# Grove_-_Mega_shield_v1_1.net
KiCad netlist of a schematic drawn in EAGLE
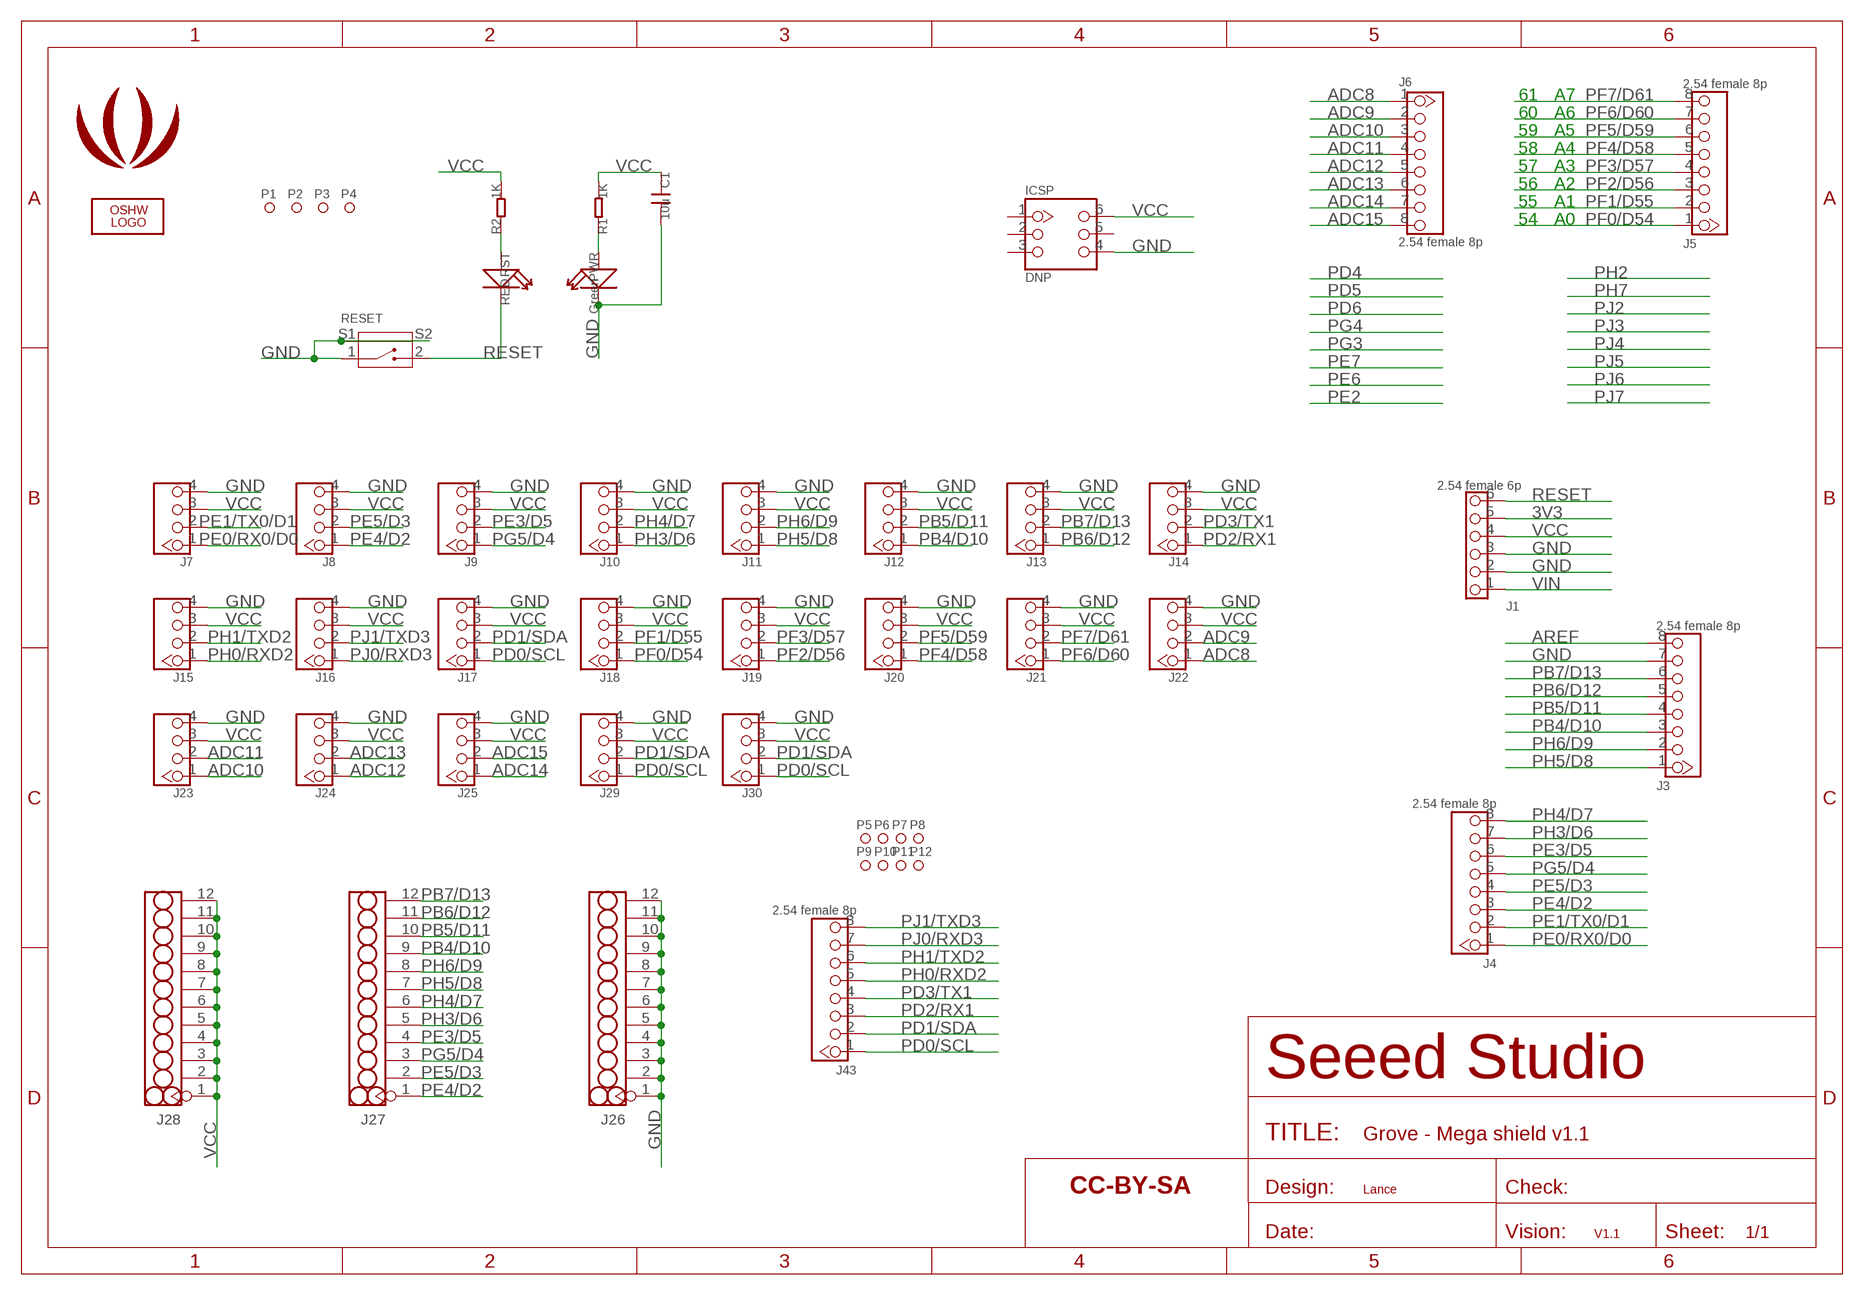
[diagram p0: schematic, sheet 1]

(export (version "E")
  (design (tool "Eeschema 10.0.6"))
  (components
    (comp (ref "C1")
      (value "10u")
      (footprint "eagle-import:0805")
      (libsource (lib "eagle-import") (part "C-0805"))
    )
    (comp (ref "ICSP")
      (value "DNP")
      (footprint "eagle-import:2X3P-2.54-LEADED-60_35")
      (libsource (lib "eagle-import") (part "HEADER-2X3P'60/35'"))
    )
    (comp (ref "J1")
      (value "2.54 female 6p")
      (footprint "eagle-import:6P-2.54-LEADED")
      (libsource (lib "eagle-import") (part "HEADER-6P-LEADED-2.54"))
    )
    (comp (ref "J3")
      (value "2.54 female 8p")
      (footprint "eagle-import:8P-2.54-LEADED")
      (libsource (lib "eagle-import") (part "HEADER-8P-2.54-LEADED"))
    )
    (comp (ref "J4")
      (value "2.54 female 8p")
      (footprint "eagle-import:8P-2.54-LEADED")
      (libsource (lib "eagle-import") (part "HEADER-8P-2.54-LEADED"))
    )
    (comp (ref "J5")
      (value "2.54 female 8p")
      (footprint "eagle-import:8P-2.54-LEADED")
      (libsource (lib "eagle-import") (part "HEADER-8P-2.54-LEADED"))
    )
    (comp (ref "J6")
      (value "2.54 female 8p")
      (footprint "eagle-import:8P-2.54-LEADED")
      (libsource (lib "eagle-import") (part "HEADER-8P-2.54-LEADED"))
    )
    (comp (ref "J7")
      (value "TWIG-2.0-LEADED'90D'")
      (footprint "eagle-import:4P-LEADED-2.0-90")
      (libsource (lib "eagle-import") (part "TWIG-2.0-LEADED'90D'"))
    )
    (comp (ref "J8")
      (value "TWIG-2.0-LEADED")
      (footprint "eagle-import:4P-LEADED-2.0")
      (libsource (lib "eagle-import") (part "TWIG-2.0-LEADED"))
    )
    (comp (ref "J9")
      (value "TWIG-2.0-LEADED")
      (footprint "eagle-import:4P-LEADED-2.0")
      (libsource (lib "eagle-import") (part "TWIG-2.0-LEADED"))
    )
    (comp (ref "J10")
      (value "TWIG-2.0-LEADED")
      (footprint "eagle-import:4P-LEADED-2.0")
      (libsource (lib "eagle-import") (part "TWIG-2.0-LEADED"))
    )
    (comp (ref "J11")
      (value "TWIG-2.0-LEADED")
      (footprint "eagle-import:4P-LEADED-2.0")
      (libsource (lib "eagle-import") (part "TWIG-2.0-LEADED"))
    )
    (comp (ref "J12")
      (value "TWIG-2.0-LEADED")
      (footprint "eagle-import:4P-LEADED-2.0")
      (libsource (lib "eagle-import") (part "TWIG-2.0-LEADED"))
    )
    (comp (ref "J13")
      (value "TWIG-2.0-LEADED")
      (footprint "eagle-import:4P-LEADED-2.0")
      (libsource (lib "eagle-import") (part "TWIG-2.0-LEADED"))
    )
    (comp (ref "J14")
      (value "TWIG-2.0-LEADED'90D'")
      (footprint "eagle-import:4P-LEADED-2.0-90")
      (libsource (lib "eagle-import") (part "TWIG-2.0-LEADED'90D'"))
    )
    (comp (ref "J15")
      (value "TWIG-2.0-LEADED'90D'")
      (footprint "eagle-import:4P-LEADED-2.0-90")
      (libsource (lib "eagle-import") (part "TWIG-2.0-LEADED'90D'"))
    )
    (comp (ref "J16")
      (value "TWIG-2.0-LEADED'90D'")
      (footprint "eagle-import:4P-LEADED-2.0-90")
      (libsource (lib "eagle-import") (part "TWIG-2.0-LEADED'90D'"))
    )
    (comp (ref "J17")
      (value "TWIG-2.0-LEADED'90D'")
      (footprint "eagle-import:4P-LEADED-2.0-90")
      (libsource (lib "eagle-import") (part "TWIG-2.0-LEADED'90D'"))
    )
    (comp (ref "J18")
      (value "TWIG-2.0-LEADED")
      (footprint "eagle-import:4P-LEADED-2.0")
      (libsource (lib "eagle-import") (part "TWIG-2.0-LEADED"))
    )
    (comp (ref "J19")
      (value "TWIG-2.0-LEADED")
      (footprint "eagle-import:4P-LEADED-2.0")
      (libsource (lib "eagle-import") (part "TWIG-2.0-LEADED"))
    )
    (comp (ref "J20")
      (value "TWIG-2.0-LEADED")
      (footprint "eagle-import:4P-LEADED-2.0")
      (libsource (lib "eagle-import") (part "TWIG-2.0-LEADED"))
    )
    (comp (ref "J21")
      (value "TWIG-2.0-LEADED")
      (footprint "eagle-import:4P-LEADED-2.0")
      (libsource (lib "eagle-import") (part "TWIG-2.0-LEADED"))
    )
    (comp (ref "J22")
      (value "TWIG-2.0-LEADED")
      (footprint "eagle-import:4P-LEADED-2.0")
      (libsource (lib "eagle-import") (part "TWIG-2.0-LEADED"))
    )
    (comp (ref "J23")
      (value "TWIG-2.0-LEADED")
      (footprint "eagle-import:4P-LEADED-2.0")
      (libsource (lib "eagle-import") (part "TWIG-2.0-LEADED"))
    )
    (comp (ref "J24")
      (value "TWIG-2.0-LEADED")
      (footprint "eagle-import:4P-LEADED-2.0")
      (libsource (lib "eagle-import") (part "TWIG-2.0-LEADED"))
    )
    (comp (ref "J25")
      (value "TWIG-2.0-LEADED")
      (footprint "eagle-import:4P-LEADED-2.0")
      (libsource (lib "eagle-import") (part "TWIG-2.0-LEADED"))
    )
    (comp (ref "J26")
      (value "HEADER-12P-2.54")
      (footprint "eagle-import:12P-2.54-LEADED")
      (libsource (lib "eagle-import") (part "HEADER-12P-2.54"))
    )
    (comp (ref "J27")
      (value "HEADER-12P-2.54")
      (footprint "eagle-import:12P-2.54-LEADED")
      (libsource (lib "eagle-import") (part "HEADER-12P-2.54"))
    )
    (comp (ref "J28")
      (value "HEADER-12P-2.54")
      (footprint "eagle-import:12P-2.54-LEADED")
      (libsource (lib "eagle-import") (part "HEADER-12P-2.54"))
    )
    (comp (ref "J29")
      (value "TWIG-2.0-LEADED")
      (footprint "eagle-import:4P-LEADED-2.0")
      (libsource (lib "eagle-import") (part "TWIG-2.0-LEADED"))
    )
    (comp (ref "J30")
      (value "TWIG-2.0-LEADED")
      (footprint "eagle-import:4P-LEADED-2.0")
      (libsource (lib "eagle-import") (part "TWIG-2.0-LEADED"))
    )
    (comp (ref "J43")
      (value "2.54 female 8p")
      (footprint "eagle-import:8P-2.54-LEADED")
      (libsource (lib "eagle-import") (part "HEADER-8P-2.54-LEADED"))
    )
    (comp (ref "LOGO1")
      (value "LOGO-OSHW-FILLX0200-NT")
      (footprint "eagle-import:OSHW_FILLX200_NOTEXT")
      (libsource (lib "eagle-import") (part "LOGO-OSHW-FILLX0200-NT"))
    )
    (comp (ref "P1")
      (value "PAD-MARK'ANNULAR'")
      (footprint "eagle-import:ROUND-MARK-1.0")
      (fields (field (name "PARTNO") "DNP"))
      (libsource (lib "eagle-import") (part "PAD-MARK'ANNULAR'"))
    )
    (comp (ref "P2")
      (value "PAD-MARK'ANNULAR'")
      (footprint "eagle-import:ROUND-MARK-1.0")
      (fields (field (name "PARTNO") "DNP"))
      (libsource (lib "eagle-import") (part "PAD-MARK'ANNULAR'"))
    )
    (comp (ref "P3")
      (value "PAD-MARK'ANNULAR'")
      (footprint "eagle-import:ROUND-MARK-1.0")
      (fields (field (name "PARTNO") "DNP"))
      (libsource (lib "eagle-import") (part "PAD-MARK'ANNULAR'"))
    )
    (comp (ref "P4")
      (value "PAD-MARK'ANNULAR'")
      (footprint "eagle-import:ROUND-MARK-1.0")
      (fields (field (name "PARTNO") "DNP"))
      (libsource (lib "eagle-import") (part "PAD-MARK'ANNULAR'"))
    )
    (comp (ref "P5")
      (value "PAD-MARK'ANNULAR'")
      (footprint "eagle-import:ROUND-MARK-1.0")
      (fields (field (name "PARTNO") "DNP"))
      (libsource (lib "eagle-import") (part "PAD-MARK'ANNULAR'"))
    )
    (comp (ref "P6")
      (value "PAD-MARK'ANNULAR'")
      (footprint "eagle-import:ROUND-MARK-1.0")
      (fields (field (name "PARTNO") "DNP"))
      (libsource (lib "eagle-import") (part "PAD-MARK'ANNULAR'"))
    )
    (comp (ref "P7")
      (value "PAD-MARK'ANNULAR'")
      (footprint "eagle-import:ROUND-MARK-1.0")
      (fields (field (name "PARTNO") "DNP"))
      (libsource (lib "eagle-import") (part "PAD-MARK'ANNULAR'"))
    )
    (comp (ref "P8")
      (value "PAD-MARK'ANNULAR'")
      (footprint "eagle-import:ROUND-MARK-1.0")
      (fields (field (name "PARTNO") "DNP"))
      (libsource (lib "eagle-import") (part "PAD-MARK'ANNULAR'"))
    )
    (comp (ref "P9")
      (value "PAD-MARK'ANNULAR'")
      (footprint "eagle-import:ROUND-MARK-1.0")
      (fields (field (name "PARTNO") "DNP"))
      (libsource (lib "eagle-import") (part "PAD-MARK'ANNULAR'"))
    )
    (comp (ref "P10")
      (value "PAD-MARK'ANNULAR'")
      (footprint "eagle-import:ROUND-MARK-1.0")
      (fields (field (name "PARTNO") "DNP"))
      (libsource (lib "eagle-import") (part "PAD-MARK'ANNULAR'"))
    )
    (comp (ref "P11")
      (value "PAD-MARK'ANNULAR'")
      (footprint "eagle-import:ROUND-MARK-1.0")
      (fields (field (name "PARTNO") "DNP"))
      (libsource (lib "eagle-import") (part "PAD-MARK'ANNULAR'"))
    )
    (comp (ref "P12")
      (value "PAD-MARK'ANNULAR'")
      (footprint "eagle-import:ROUND-MARK-1.0")
      (fields (field (name "PARTNO") "DNP"))
      (libsource (lib "eagle-import") (part "PAD-MARK'ANNULAR'"))
    )
    (comp (ref "PWR")
      (value "Green")
      (footprint "eagle-import:D0603")
      (libsource (lib "eagle-import") (part "LED-0603"))
    )
    (comp (ref "R1")
      (value "1K")
      (footprint "eagle-import:0402")
      (libsource (lib "eagle-import") (part "R-0402"))
    )
    (comp (ref "R2")
      (value "1K")
      (footprint "eagle-import:0402")
      (libsource (lib "eagle-import") (part "R-0402"))
    )
    (comp (ref "RESET")
      (value "BUTTON-2+2P'TS-1188E'")
      (footprint "eagle-import:4P-SMD-L7.0_W3.5_H3.5MM-90D")
      (libsource (lib "eagle-import") (part "BUTTON-2+2P'TS-1188E'"))
    )
    (comp (ref "RST")
      (value "RED")
      (footprint "eagle-import:D0603")
      (libsource (lib "eagle-import") (part "LED-0603"))
    )
    (comp (ref "U$1")
      (value "LOGO-SEEEDSTUDIO-SILK")
      (footprint "eagle-import:LOGO_SILK")
      (libsource (lib "eagle-import") (part "LOGO-SEEEDSTUDIO-SILK"))
    )
    (comp (ref "U$2")
      (value "LOGO-SEEEDSTUDIO-COPPER")
      (footprint "eagle-import:LOGO_COPPER")
      (libsource (lib "eagle-import") (part "LOGO-SEEEDSTUDIO-COPPER"))
    )
    (comp (ref "U$3")
      (value "SEEEDSTUDIO-OPEN-SCH-FRAME")
      (footprint "eagle-import:SEEEDSTUDIO-PCB-FRAME")
      (libsource (lib "eagle-import") (part "SEEEDSTUDIO-OPEN-SCH-FRAME"))
    )
  )
  (nets
    (net (code "1") (name "/3V3") (class "Default")
      (node (ref "J1") (pin "5") (pinfunction "5_5") (pintype "bidirectional"))
    )
    (net (code "2") (name "/ADC8") (class "Default")
      (node (ref "J22") (pin "1") (pinfunction "1_1") (pintype "bidirectional"))
      (node (ref "J6") (pin "1") (pinfunction "1_1") (pintype "bidirectional"))
    )
    (net (code "3") (name "/ADC9") (class "Default")
      (node (ref "J22") (pin "2") (pinfunction "2_2") (pintype "bidirectional"))
      (node (ref "J6") (pin "2") (pinfunction "2_2") (pintype "bidirectional"))
    )
    (net (code "4") (name "/ADC10") (class "Default")
      (node (ref "J23") (pin "1") (pinfunction "1_1") (pintype "bidirectional"))
      (node (ref "J6") (pin "3") (pinfunction "3_3") (pintype "bidirectional"))
    )
    (net (code "5") (name "/ADC11") (class "Default")
      (node (ref "J23") (pin "2") (pinfunction "2_2") (pintype "bidirectional"))
      (node (ref "J6") (pin "4") (pinfunction "4_4") (pintype "bidirectional"))
    )
    (net (code "6") (name "/ADC12") (class "Default")
      (node (ref "J24") (pin "1") (pinfunction "1_1") (pintype "bidirectional"))
      (node (ref "J6") (pin "5") (pinfunction "5_5") (pintype "bidirectional"))
    )
    (net (code "7") (name "/ADC13") (class "Default")
      (node (ref "J24") (pin "2") (pinfunction "2_2") (pintype "bidirectional"))
      (node (ref "J6") (pin "6") (pinfunction "6_6") (pintype "bidirectional"))
    )
    (net (code "8") (name "/ADC14") (class "Default")
      (node (ref "J25") (pin "1") (pinfunction "1_1") (pintype "bidirectional"))
      (node (ref "J6") (pin "7") (pinfunction "7_7") (pintype "bidirectional"))
    )
    (net (code "9") (name "/ADC15") (class "Default")
      (node (ref "J25") (pin "2") (pinfunction "2_2") (pintype "bidirectional"))
      (node (ref "J6") (pin "8") (pinfunction "8_8") (pintype "bidirectional"))
    )
    (net (code "10") (name "/AREF") (class "Default")
      (node (ref "J3") (pin "8") (pinfunction "8_8") (pintype "bidirectional"))
    )
    (net (code "11") (name "/GND") (class "Default")
      (node (ref "C1") (pin "2") (pinfunction "2_2") (pintype "passive"))
      (node (ref "ICSP") (pin "4") (pinfunction "4_4") (pintype "bidirectional"))
      (node (ref "J1") (pin "2") (pinfunction "2_2") (pintype "bidirectional"))
      (node (ref "J1") (pin "3") (pinfunction "3_3") (pintype "bidirectional"))
      (node (ref "J10") (pin "4") (pinfunction "4_4") (pintype "bidirectional"))
      (node (ref "J11") (pin "4") (pinfunction "4_4") (pintype "bidirectional"))
      (node (ref "J12") (pin "4") (pinfunction "4_4") (pintype "bidirectional"))
      (node (ref "J13") (pin "4") (pinfunction "4_4") (pintype "bidirectional"))
      (node (ref "J14") (pin "4") (pinfunction "4_4") (pintype "bidirectional"))
      (node (ref "J15") (pin "4") (pinfunction "4_4") (pintype "bidirectional"))
      (node (ref "J16") (pin "4") (pinfunction "4_4") (pintype "bidirectional"))
      (node (ref "J17") (pin "4") (pinfunction "4_4") (pintype "bidirectional"))
      (node (ref "J18") (pin "4") (pinfunction "4_4") (pintype "bidirectional"))
      (node (ref "J19") (pin "4") (pinfunction "4_4") (pintype "bidirectional"))
      (node (ref "J20") (pin "4") (pinfunction "4_4") (pintype "bidirectional"))
      (node (ref "J21") (pin "4") (pinfunction "4_4") (pintype "bidirectional"))
      (node (ref "J22") (pin "4") (pinfunction "4_4") (pintype "bidirectional"))
      (node (ref "J23") (pin "4") (pinfunction "4_4") (pintype "bidirectional"))
      (node (ref "J24") (pin "4") (pinfunction "4_4") (pintype "bidirectional"))
      (node (ref "J25") (pin "4") (pinfunction "4_4") (pintype "bidirectional"))
      (node (ref "J26") (pin "1") (pinfunction "1_1") (pintype "bidirectional"))
      (node (ref "J26") (pin "10") (pinfunction "10_10") (pintype "bidirectional"))
      (node (ref "J26") (pin "11") (pinfunction "11_11") (pintype "bidirectional"))
      (node (ref "J26") (pin "12") (pinfunction "12_12") (pintype "bidirectional"))
      (node (ref "J26") (pin "2") (pinfunction "2_2") (pintype "bidirectional"))
      (node (ref "J26") (pin "3") (pinfunction "3_3") (pintype "bidirectional"))
      (node (ref "J26") (pin "4") (pinfunction "4_4") (pintype "bidirectional"))
      (node (ref "J26") (pin "5") (pinfunction "5_5") (pintype "bidirectional"))
      (node (ref "J26") (pin "6") (pinfunction "6_6") (pintype "bidirectional"))
      (node (ref "J26") (pin "7") (pinfunction "7_7") (pintype "bidirectional"))
      (node (ref "J26") (pin "8") (pinfunction "8_8") (pintype "bidirectional"))
      (node (ref "J26") (pin "9") (pinfunction "9_9") (pintype "bidirectional"))
      (node (ref "J29") (pin "4") (pinfunction "4_4") (pintype "bidirectional"))
      (node (ref "J3") (pin "7") (pinfunction "7_7") (pintype "bidirectional"))
      (node (ref "J30") (pin "4") (pinfunction "4_4") (pintype "bidirectional"))
      (node (ref "J7") (pin "4") (pinfunction "4_4") (pintype "bidirectional"))
      (node (ref "J8") (pin "4") (pinfunction "4_4") (pintype "bidirectional"))
      (node (ref "J9") (pin "4") (pinfunction "4_4") (pintype "bidirectional"))
      (node (ref "PWR") (pin "-") (pinfunction "-_-") (pintype "passive"))
      (node (ref "RESET") (pin "1") (pinfunction "1_1") (pintype "bidirectional"))
      (node (ref "RESET") (pin "S1") (pinfunction "S1_S1") (pintype "bidirectional"))
      (node (ref "RESET") (pin "S2") (pinfunction "S2_S2") (pintype "bidirectional"))
    )
    (net (code "12") (name "/PB4{slash}D10") (class "Default")
      (node (ref "J12") (pin "1") (pinfunction "1_1") (pintype "bidirectional"))
      (node (ref "J27") (pin "9") (pinfunction "9_9") (pintype "bidirectional"))
      (node (ref "J3") (pin "3") (pinfunction "3_3") (pintype "bidirectional"))
    )
    (net (code "13") (name "/PB5{slash}D11") (class "Default")
      (node (ref "J12") (pin "2") (pinfunction "2_2") (pintype "bidirectional"))
      (node (ref "J27") (pin "10") (pinfunction "10_10") (pintype "bidirectional"))
      (node (ref "J3") (pin "4") (pinfunction "4_4") (pintype "bidirectional"))
    )
    (net (code "14") (name "/PB6{slash}D12") (class "Default")
      (node (ref "J13") (pin "1") (pinfunction "1_1") (pintype "bidirectional"))
      (node (ref "J27") (pin "11") (pinfunction "11_11") (pintype "bidirectional"))
      (node (ref "J3") (pin "5") (pinfunction "5_5") (pintype "bidirectional"))
    )
    (net (code "15") (name "/PB7{slash}D13") (class "Default")
      (node (ref "J13") (pin "2") (pinfunction "2_2") (pintype "bidirectional"))
      (node (ref "J27") (pin "12") (pinfunction "12_12") (pintype "bidirectional"))
      (node (ref "J3") (pin "6") (pinfunction "6_6") (pintype "bidirectional"))
    )
    (net (code "16") (name "/PD0{slash}SCL") (class "Default")
      (node (ref "J17") (pin "1") (pinfunction "1_1") (pintype "bidirectional"))
      (node (ref "J29") (pin "1") (pinfunction "1_1") (pintype "bidirectional"))
      (node (ref "J30") (pin "1") (pinfunction "1_1") (pintype "bidirectional"))
      (node (ref "J43") (pin "1") (pinfunction "1_1") (pintype "bidirectional"))
    )
    (net (code "17") (name "/PD1{slash}SDA") (class "Default")
      (node (ref "J17") (pin "2") (pinfunction "2_2") (pintype "bidirectional"))
      (node (ref "J29") (pin "2") (pinfunction "2_2") (pintype "bidirectional"))
      (node (ref "J30") (pin "2") (pinfunction "2_2") (pintype "bidirectional"))
      (node (ref "J43") (pin "2") (pinfunction "2_2") (pintype "bidirectional"))
    )
    (net (code "18") (name "/PD2{slash}RX1") (class "Default")
      (node (ref "J14") (pin "1") (pinfunction "1_1") (pintype "bidirectional"))
      (node (ref "J43") (pin "3") (pinfunction "3_3") (pintype "bidirectional"))
    )
    (net (code "19") (name "/PD3{slash}TX1") (class "Default")
      (node (ref "J14") (pin "2") (pinfunction "2_2") (pintype "bidirectional"))
      (node (ref "J43") (pin "4") (pinfunction "4_4") (pintype "bidirectional"))
    )
    (net (code "23") (name "/PE0{slash}RX0{slash}D0") (class "Default")
      (node (ref "J4") (pin "1") (pinfunction "1_1") (pintype "bidirectional"))
      (node (ref "J7") (pin "1") (pinfunction "1_1") (pintype "bidirectional"))
    )
    (net (code "24") (name "/PE1{slash}TX0{slash}D1") (class "Default")
      (node (ref "J4") (pin "2") (pinfunction "2_2") (pintype "bidirectional"))
      (node (ref "J7") (pin "2") (pinfunction "2_2") (pintype "bidirectional"))
    )
    (net (code "26") (name "/PE3{slash}D5") (class "Default")
      (node (ref "J27") (pin "4") (pinfunction "4_4") (pintype "bidirectional"))
      (node (ref "J4") (pin "6") (pinfunction "6_6") (pintype "bidirectional"))
      (node (ref "J9") (pin "2") (pinfunction "2_2") (pintype "bidirectional"))
    )
    (net (code "27") (name "/PE4{slash}D2") (class "Default")
      (node (ref "J27") (pin "1") (pinfunction "1_1") (pintype "bidirectional"))
      (node (ref "J4") (pin "3") (pinfunction "3_3") (pintype "bidirectional"))
      (node (ref "J8") (pin "1") (pinfunction "1_1") (pintype "bidirectional"))
    )
    (net (code "28") (name "/PE5{slash}D3") (class "Default")
      (node (ref "J27") (pin "2") (pinfunction "2_2") (pintype "bidirectional"))
      (node (ref "J4") (pin "4") (pinfunction "4_4") (pintype "bidirectional"))
      (node (ref "J8") (pin "2") (pinfunction "2_2") (pintype "bidirectional"))
    )
    (net (code "31") (name "/PF0{slash}D54") (class "Default")
      (node (ref "J18") (pin "1") (pinfunction "1_1") (pintype "bidirectional"))
      (node (ref "J5") (pin "1") (pinfunction "1_1") (pintype "bidirectional"))
    )
    (net (code "32") (name "/PF1{slash}D55") (class "Default")
      (node (ref "J18") (pin "2") (pinfunction "2_2") (pintype "bidirectional"))
      (node (ref "J5") (pin "2") (pinfunction "2_2") (pintype "bidirectional"))
    )
    (net (code "33") (name "/PF2{slash}D56") (class "Default")
      (node (ref "J19") (pin "1") (pinfunction "1_1") (pintype "bidirectional"))
      (node (ref "J5") (pin "3") (pinfunction "3_3") (pintype "bidirectional"))
    )
    (net (code "34") (name "/PF3{slash}D57") (class "Default")
      (node (ref "J19") (pin "2") (pinfunction "2_2") (pintype "bidirectional"))
      (node (ref "J5") (pin "4") (pinfunction "4_4") (pintype "bidirectional"))
    )
    (net (code "35") (name "/PF4{slash}D58") (class "Default")
      (node (ref "J20") (pin "1") (pinfunction "1_1") (pintype "bidirectional"))
      (node (ref "J5") (pin "5") (pinfunction "5_5") (pintype "bidirectional"))
    )
    (net (code "36") (name "/PF5{slash}D59") (class "Default")
      (node (ref "J20") (pin "2") (pinfunction "2_2") (pintype "bidirectional"))
      (node (ref "J5") (pin "6") (pinfunction "6_6") (pintype "bidirectional"))
    )
    (net (code "37") (name "/PF6{slash}D60") (class "Default")
      (node (ref "J21") (pin "1") (pinfunction "1_1") (pintype "bidirectional"))
      (node (ref "J5") (pin "7") (pinfunction "7_7") (pintype "bidirectional"))
    )
    (net (code "38") (name "/PF7{slash}D61") (class "Default")
      (node (ref "J21") (pin "2") (pinfunction "2_2") (pintype "bidirectional"))
      (node (ref "J5") (pin "8") (pinfunction "8_8") (pintype "bidirectional"))
    )
    (net (code "41") (name "/PG5{slash}D4") (class "Default")
      (node (ref "J27") (pin "3") (pinfunction "3_3") (pintype "bidirectional"))
      (node (ref "J4") (pin "5") (pinfunction "5_5") (pintype "bidirectional"))
      (node (ref "J9") (pin "1") (pinfunction "1_1") (pintype "bidirectional"))
    )
    (net (code "42") (name "/PH0{slash}RXD2") (class "Default")
      (node (ref "J15") (pin "1") (pinfunction "1_1") (pintype "bidirectional"))
      (node (ref "J43") (pin "5") (pinfunction "5_5") (pintype "bidirectional"))
    )
    (net (code "43") (name "/PH1{slash}TXD2") (class "Default")
      (node (ref "J15") (pin "2") (pinfunction "2_2") (pintype "bidirectional"))
      (node (ref "J43") (pin "6") (pinfunction "6_6") (pintype "bidirectional"))
    )
    (net (code "45") (name "/PH3{slash}D6") (class "Default")
      (node (ref "J10") (pin "1") (pinfunction "1_1") (pintype "bidirectional"))
      (node (ref "J27") (pin "5") (pinfunction "5_5") (pintype "bidirectional"))
      (node (ref "J4") (pin "7") (pinfunction "7_7") (pintype "bidirectional"))
    )
    (net (code "46") (name "/PH4{slash}D7") (class "Default")
      (node (ref "J10") (pin "2") (pinfunction "2_2") (pintype "bidirectional"))
      (node (ref "J27") (pin "6") (pinfunction "6_6") (pintype "bidirectional"))
      (node (ref "J4") (pin "8") (pinfunction "8_8") (pintype "bidirectional"))
    )
    (net (code "47") (name "/PH5{slash}D8") (class "Default")
      (node (ref "J11") (pin "1") (pinfunction "1_1") (pintype "bidirectional"))
      (node (ref "J27") (pin "7") (pinfunction "7_7") (pintype "bidirectional"))
      (node (ref "J3") (pin "1") (pinfunction "1_1") (pintype "bidirectional"))
    )
    (net (code "48") (name "/PH6{slash}D9") (class "Default")
      (node (ref "J11") (pin "2") (pinfunction "2_2") (pintype "bidirectional"))
      (node (ref "J27") (pin "8") (pinfunction "8_8") (pintype "bidirectional"))
      (node (ref "J3") (pin "2") (pinfunction "2_2") (pintype "bidirectional"))
    )
    (net (code "50") (name "/PJ0{slash}RXD3") (class "Default")
      (node (ref "J16") (pin "1") (pinfunction "1_1") (pintype "bidirectional"))
      (node (ref "J43") (pin "7") (pinfunction "7_7") (pintype "bidirectional"))
    )
    (net (code "51") (name "/PJ1{slash}TXD3") (class "Default")
      (node (ref "J16") (pin "2") (pinfunction "2_2") (pintype "bidirectional"))
      (node (ref "J43") (pin "8") (pinfunction "8_8") (pintype "bidirectional"))
    )
    (net (code "58") (name "/RESET") (class "Default")
      (node (ref "J1") (pin "6") (pinfunction "6_6") (pintype "bidirectional"))
      (node (ref "RESET") (pin "2") (pinfunction "2_2") (pintype "bidirectional"))
      (node (ref "RST") (pin "-") (pinfunction "-_-") (pintype "passive"))
    )
    (net (code "59") (name "/VCC") (class "Default")
      (node (ref "C1") (pin "1") (pinfunction "1_1") (pintype "passive"))
      (node (ref "ICSP") (pin "6") (pinfunction "6_6") (pintype "bidirectional"))
      (node (ref "J1") (pin "4") (pinfunction "4_4") (pintype "bidirectional"))
      (node (ref "J10") (pin "3") (pinfunction "3_3") (pintype "bidirectional"))
      (node (ref "J11") (pin "3") (pinfunction "3_3") (pintype "bidirectional"))
      (node (ref "J12") (pin "3") (pinfunction "3_3") (pintype "bidirectional"))
      (node (ref "J13") (pin "3") (pinfunction "3_3") (pintype "bidirectional"))
      (node (ref "J14") (pin "3") (pinfunction "3_3") (pintype "bidirectional"))
      (node (ref "J15") (pin "3") (pinfunction "3_3") (pintype "bidirectional"))
      (node (ref "J16") (pin "3") (pinfunction "3_3") (pintype "bidirectional"))
      (node (ref "J17") (pin "3") (pinfunction "3_3") (pintype "bidirectional"))
      (node (ref "J18") (pin "3") (pinfunction "3_3") (pintype "bidirectional"))
      (node (ref "J19") (pin "3") (pinfunction "3_3") (pintype "bidirectional"))
      (node (ref "J20") (pin "3") (pinfunction "3_3") (pintype "bidirectional"))
      (node (ref "J21") (pin "3") (pinfunction "3_3") (pintype "bidirectional"))
      (node (ref "J22") (pin "3") (pinfunction "3_3") (pintype "bidirectional"))
      (node (ref "J23") (pin "3") (pinfunction "3_3") (pintype "bidirectional"))
      (node (ref "J24") (pin "3") (pinfunction "3_3") (pintype "bidirectional"))
      (node (ref "J25") (pin "3") (pinfunction "3_3") (pintype "bidirectional"))
      (node (ref "J28") (pin "1") (pinfunction "1_1") (pintype "bidirectional"))
      (node (ref "J28") (pin "10") (pinfunction "10_10") (pintype "bidirectional"))
      (node (ref "J28") (pin "11") (pinfunction "11_11") (pintype "bidirectional"))
      (node (ref "J28") (pin "12") (pinfunction "12_12") (pintype "bidirectional"))
      (node (ref "J28") (pin "2") (pinfunction "2_2") (pintype "bidirectional"))
      (node (ref "J28") (pin "3") (pinfunction "3_3") (pintype "bidirectional"))
      (node (ref "J28") (pin "4") (pinfunction "4_4") (pintype "bidirectional"))
      (node (ref "J28") (pin "5") (pinfunction "5_5") (pintype "bidirectional"))
      (node (ref "J28") (pin "6") (pinfunction "6_6") (pintype "bidirectional"))
      (node (ref "J28") (pin "7") (pinfunction "7_7") (pintype "bidirectional"))
      (node (ref "J28") (pin "8") (pinfunction "8_8") (pintype "bidirectional"))
      (node (ref "J28") (pin "9") (pinfunction "9_9") (pintype "bidirectional"))
      (node (ref "J29") (pin "3") (pinfunction "3_3") (pintype "bidirectional"))
      (node (ref "J30") (pin "3") (pinfunction "3_3") (pintype "bidirectional"))
      (node (ref "J7") (pin "3") (pinfunction "3_3") (pintype "bidirectional"))
      (node (ref "J8") (pin "3") (pinfunction "3_3") (pintype "bidirectional"))
      (node (ref "J9") (pin "3") (pinfunction "3_3") (pintype "bidirectional"))
      (node (ref "R1") (pin "2") (pinfunction "2_2") (pintype "passive"))
      (node (ref "R2") (pin "2") (pinfunction "2_2") (pintype "passive"))
    )
    (net (code "60") (name "/VIN") (class "Default")
      (node (ref "J1") (pin "1") (pinfunction "1_1") (pintype "bidirectional"))
    )
    (net (code "61") (name "Net-(PWR-Pad+)") (class "Default")
      (node (ref "PWR") (pin "+") (pinfunction "+_+") (pintype "passive"))
      (node (ref "R1") (pin "1") (pinfunction "1_1") (pintype "passive"))
    )
    (net (code "62") (name "Net-(R2-Pad1)") (class "Default")
      (node (ref "R2") (pin "1") (pinfunction "1_1") (pintype "passive"))
      (node (ref "RST") (pin "+") (pinfunction "+_+") (pintype "passive"))
    )
    (net (code "63") (name "unconnected-(ICSP-Pad1)") (class "Default")
      (node (ref "ICSP") (pin "1") (pinfunction "1_1") (pintype "bidirectional"))
    )
    (net (code "64") (name "unconnected-(ICSP-Pad2)") (class "Default")
      (node (ref "ICSP") (pin "2") (pinfunction "2_2") (pintype "bidirectional"))
    )
    (net (code "65") (name "unconnected-(ICSP-Pad3)") (class "Default")
      (node (ref "ICSP") (pin "3") (pinfunction "3_3") (pintype "bidirectional"))
    )
    (net (code "66") (name "unconnected-(ICSP-Pad5)") (class "Default")
      (node (ref "ICSP") (pin "5") (pinfunction "5_5") (pintype "bidirectional"))
    )
  )
)
